# FAN-plus40-SHIM.net
KiCad netlist of a schematic drawn in EAGLE
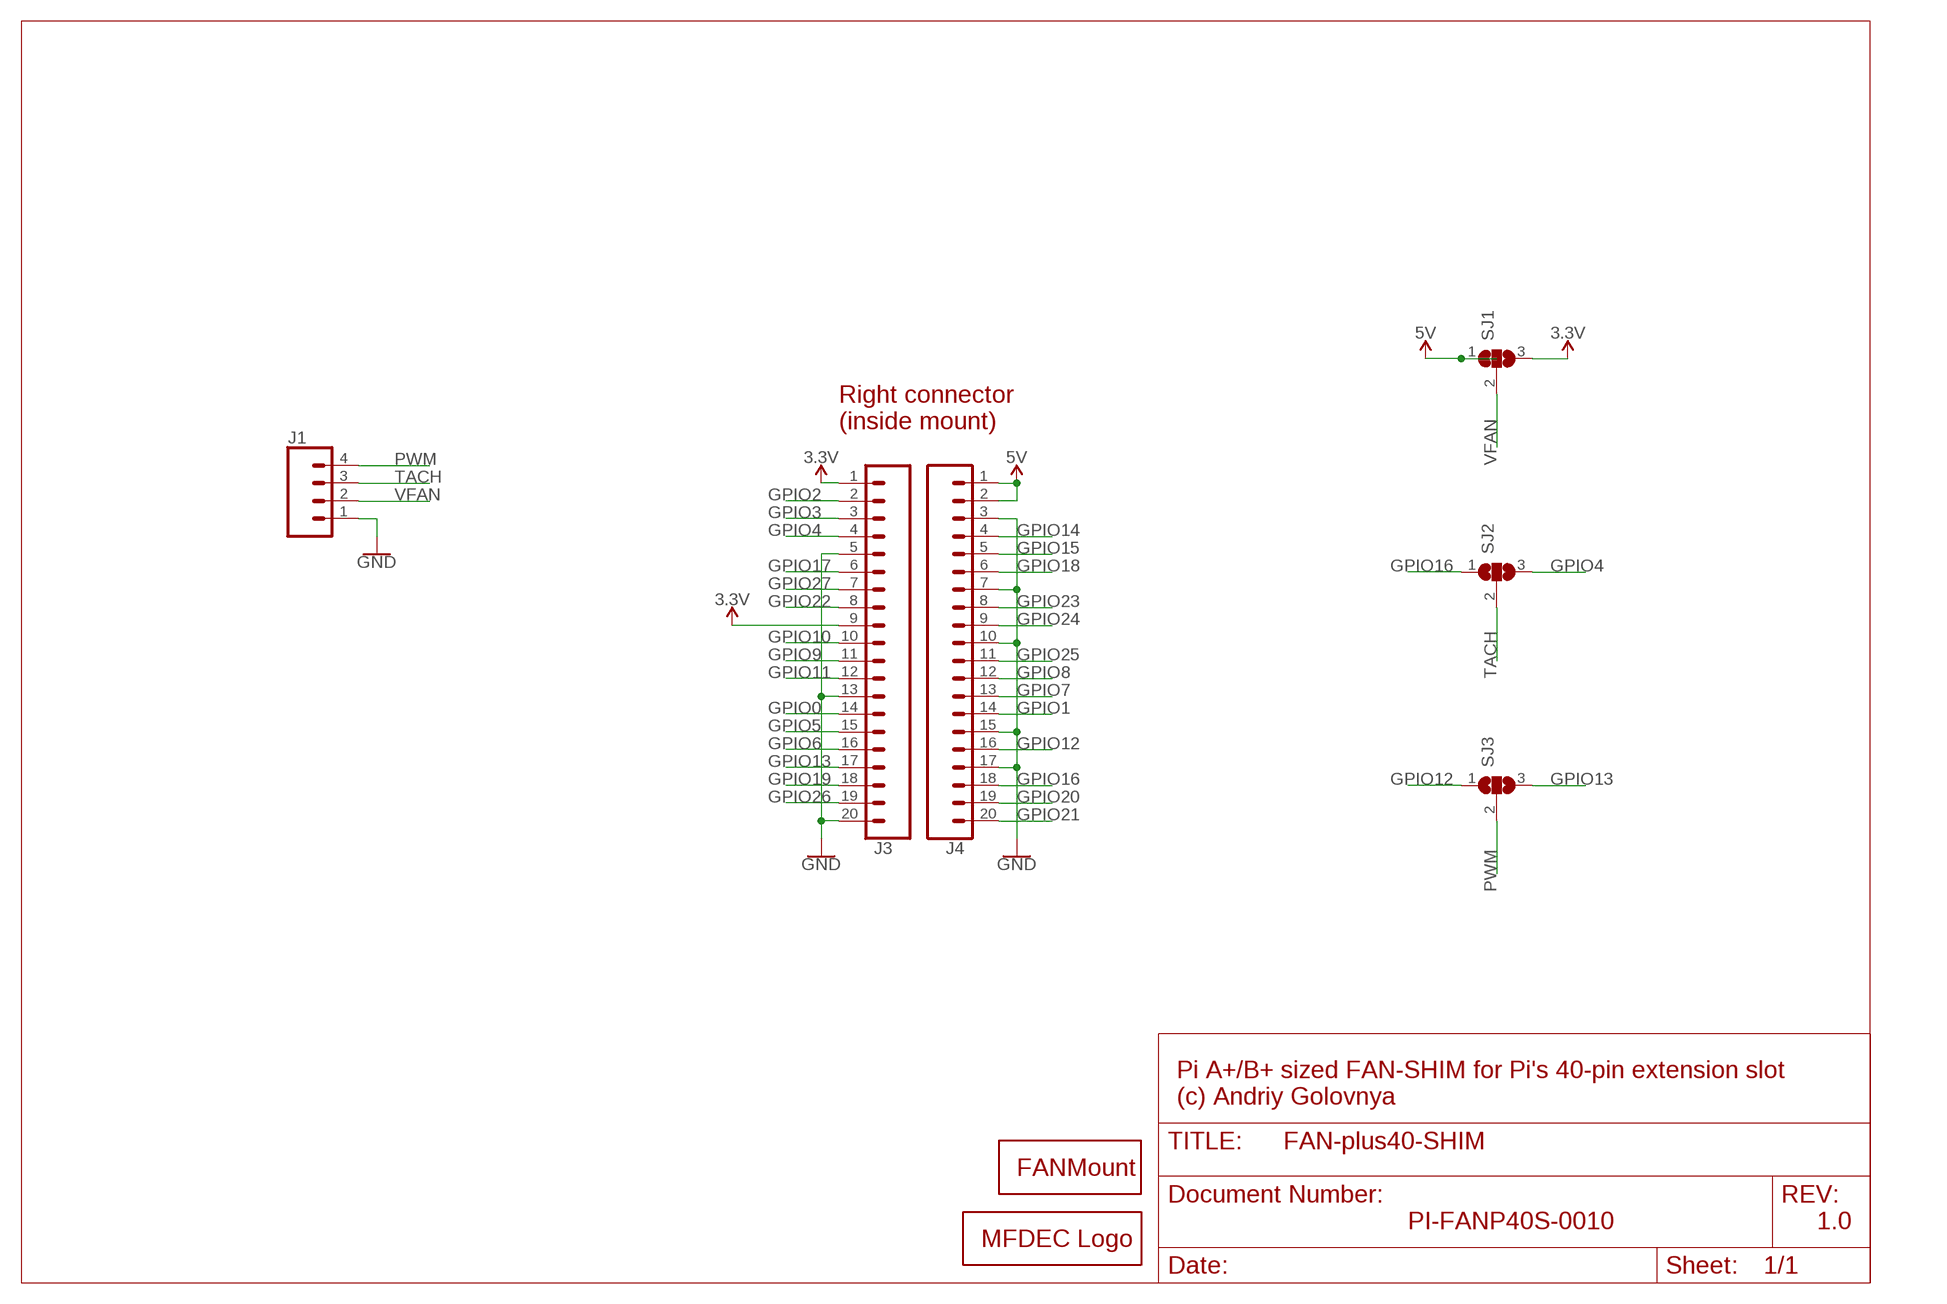
[diagram p0: schematic, sheet 1]

(export (version "E")
  (design (tool "Eeschema 10.0.6"))
  (components
    (comp (ref "FAN1")
      (value "FAN40HO")
      (footprint "eagle-import:FAN40HO")
      (libsource (lib "eagle-import") (part "FAN40HO"))
    )
    (comp (ref "J1")
      (value "CONN_04")
      (footprint "eagle-import:1X04")
      (libsource (lib "eagle-import") (part "CONN_04"))
    )
    (comp (ref "J3")
      (value "CONN_20LOCK")
      (footprint "eagle-import:1X20_LOCK")
      (libsource (lib "eagle-import") (part "CONN_20LOCK"))
    )
    (comp (ref "J4")
      (value "CONN_20LOCK")
      (footprint "eagle-import:1X20_LOCK")
      (libsource (lib "eagle-import") (part "CONN_20LOCK"))
    )
    (comp (ref "LOGO1")
      (value "MFDECLOGO_L_40MM")
      (footprint "eagle-import:MFDEC_L_40MM")
      (libsource (lib "eagle-import") (part "MFDECLOGO_L_40MM"))
    )
    (comp (ref "SJ1")
      (value "SJ2")
      (footprint "eagle-import:SJ_2")
      (libsource (lib "eagle-import") (part "SJ2"))
    )
    (comp (ref "SJ2")
      (value "SJ2")
      (footprint "eagle-import:SJ_2")
      (libsource (lib "eagle-import") (part "SJ2"))
    )
    (comp (ref "SJ3")
      (value "SJ2")
      (footprint "eagle-import:SJ_2")
      (libsource (lib "eagle-import") (part "SJ2"))
    )
  )
  (nets
    (net (code "1") (name "/GPIO0") (class "Default")
      (node (ref "J3") (pin "14") (pinfunction "14_14") (pintype "passive"))
    )
    (net (code "2") (name "/GPIO1") (class "Default")
      (node (ref "J4") (pin "14") (pinfunction "14_14") (pintype "passive"))
    )
    (net (code "3") (name "/GPIO2") (class "Default")
      (node (ref "J3") (pin "2") (pinfunction "2_2") (pintype "passive"))
    )
    (net (code "4") (name "/GPIO3") (class "Default")
      (node (ref "J3") (pin "3") (pinfunction "3_3") (pintype "passive"))
    )
    (net (code "5") (name "/GPIO4") (class "Default")
      (node (ref "J3") (pin "4") (pinfunction "4_4") (pintype "passive"))
      (node (ref "SJ2") (pin "3") (pinfunction "3_3") (pintype "passive"))
    )
    (net (code "6") (name "/GPIO5") (class "Default")
      (node (ref "J3") (pin "15") (pinfunction "15_15") (pintype "passive"))
    )
    (net (code "7") (name "/GPIO6") (class "Default")
      (node (ref "J3") (pin "16") (pinfunction "16_16") (pintype "passive"))
    )
    (net (code "8") (name "/GPIO7") (class "Default")
      (node (ref "J4") (pin "13") (pinfunction "13_13") (pintype "passive"))
    )
    (net (code "9") (name "/GPIO8") (class "Default")
      (node (ref "J4") (pin "12") (pinfunction "12_12") (pintype "passive"))
    )
    (net (code "10") (name "/GPIO9") (class "Default")
      (node (ref "J3") (pin "11") (pinfunction "11_11") (pintype "passive"))
    )
    (net (code "11") (name "/GPIO10") (class "Default")
      (node (ref "J3") (pin "10") (pinfunction "10_10") (pintype "passive"))
    )
    (net (code "12") (name "/GPIO11") (class "Default")
      (node (ref "J3") (pin "12") (pinfunction "12_12") (pintype "passive"))
    )
    (net (code "13") (name "/GPIO12") (class "Default")
      (node (ref "J4") (pin "16") (pinfunction "16_16") (pintype "passive"))
      (node (ref "SJ3") (pin "1") (pinfunction "1_1") (pintype "passive"))
    )
    (net (code "14") (name "/GPIO13") (class "Default")
      (node (ref "J3") (pin "17") (pinfunction "17_17") (pintype "passive"))
      (node (ref "SJ3") (pin "3") (pinfunction "3_3") (pintype "passive"))
    )
    (net (code "15") (name "/GPIO14") (class "Default")
      (node (ref "J4") (pin "4") (pinfunction "4_4") (pintype "passive"))
    )
    (net (code "16") (name "/GPIO15") (class "Default")
      (node (ref "J4") (pin "5") (pinfunction "5_5") (pintype "passive"))
    )
    (net (code "17") (name "/GPIO16") (class "Default")
      (node (ref "J4") (pin "18") (pinfunction "18_18") (pintype "passive"))
      (node (ref "SJ2") (pin "1") (pinfunction "1_1") (pintype "passive"))
    )
    (net (code "18") (name "/GPIO17") (class "Default")
      (node (ref "J3") (pin "6") (pinfunction "6_6") (pintype "passive"))
    )
    (net (code "19") (name "/GPIO18") (class "Default")
      (node (ref "J4") (pin "6") (pinfunction "6_6") (pintype "passive"))
    )
    (net (code "20") (name "/GPIO19") (class "Default")
      (node (ref "J3") (pin "18") (pinfunction "18_18") (pintype "passive"))
    )
    (net (code "21") (name "/GPIO20") (class "Default")
      (node (ref "J4") (pin "19") (pinfunction "19_19") (pintype "passive"))
    )
    (net (code "22") (name "/GPIO21") (class "Default")
      (node (ref "J4") (pin "20") (pinfunction "20_20") (pintype "passive"))
    )
    (net (code "23") (name "/GPIO22") (class "Default")
      (node (ref "J3") (pin "8") (pinfunction "8_8") (pintype "passive"))
    )
    (net (code "24") (name "/GPIO23") (class "Default")
      (node (ref "J4") (pin "8") (pinfunction "8_8") (pintype "passive"))
    )
    (net (code "25") (name "/GPIO24") (class "Default")
      (node (ref "J4") (pin "9") (pinfunction "9_9") (pintype "passive"))
    )
    (net (code "26") (name "/GPIO25") (class "Default")
      (node (ref "J4") (pin "11") (pinfunction "11_11") (pintype "passive"))
    )
    (net (code "27") (name "/GPIO26") (class "Default")
      (node (ref "J3") (pin "19") (pinfunction "19_19") (pintype "passive"))
    )
    (net (code "28") (name "/GPIO27") (class "Default")
      (node (ref "J3") (pin "7") (pinfunction "7_7") (pintype "passive"))
    )
    (net (code "29") (name "/PWM") (class "Default")
      (node (ref "J1") (pin "4") (pinfunction "4_4") (pintype "passive"))
      (node (ref "SJ3") (pin "2") (pinfunction "2_2") (pintype "passive"))
    )
    (net (code "30") (name "/TACH") (class "Default")
      (node (ref "J1") (pin "3") (pinfunction "3_3") (pintype "passive"))
      (node (ref "SJ2") (pin "2") (pinfunction "2_2") (pintype "passive"))
    )
    (net (code "31") (name "/VFAN") (class "Default")
      (node (ref "J1") (pin "2") (pinfunction "2_2") (pintype "passive"))
      (node (ref "SJ1") (pin "2") (pinfunction "2_2") (pintype "passive"))
    )
    (net (code "32") (name "3.3V") (class "Default")
      (node (ref "J3") (pin "1") (pinfunction "1_1") (pintype "passive"))
      (node (ref "J3") (pin "9") (pinfunction "9_9") (pintype "passive"))
      (node (ref "SJ1") (pin "3") (pinfunction "3_3") (pintype "passive"))
    )
    (net (code "33") (name "5V") (class "Default")
      (node (ref "J4") (pin "1") (pinfunction "1_1") (pintype "passive"))
      (node (ref "J4") (pin "2") (pinfunction "2_2") (pintype "passive"))
      (node (ref "SJ1") (pin "1") (pinfunction "1_1") (pintype "passive"))
    )
    (net (code "34") (name "GND") (class "Default")
      (node (ref "J1") (pin "1") (pinfunction "1_1") (pintype "passive"))
      (node (ref "J3") (pin "13") (pinfunction "13_13") (pintype "passive"))
      (node (ref "J3") (pin "20") (pinfunction "20_20") (pintype "passive"))
      (node (ref "J3") (pin "5") (pinfunction "5_5") (pintype "passive"))
      (node (ref "J4") (pin "10") (pinfunction "10_10") (pintype "passive"))
      (node (ref "J4") (pin "15") (pinfunction "15_15") (pintype "passive"))
      (node (ref "J4") (pin "17") (pinfunction "17_17") (pintype "passive"))
      (node (ref "J4") (pin "3") (pinfunction "3_3") (pintype "passive"))
      (node (ref "J4") (pin "7") (pinfunction "7_7") (pintype "passive"))
    )
  )
)
